# Thermit.net
KiCad netlist of a schematic drawn in Altium Designer
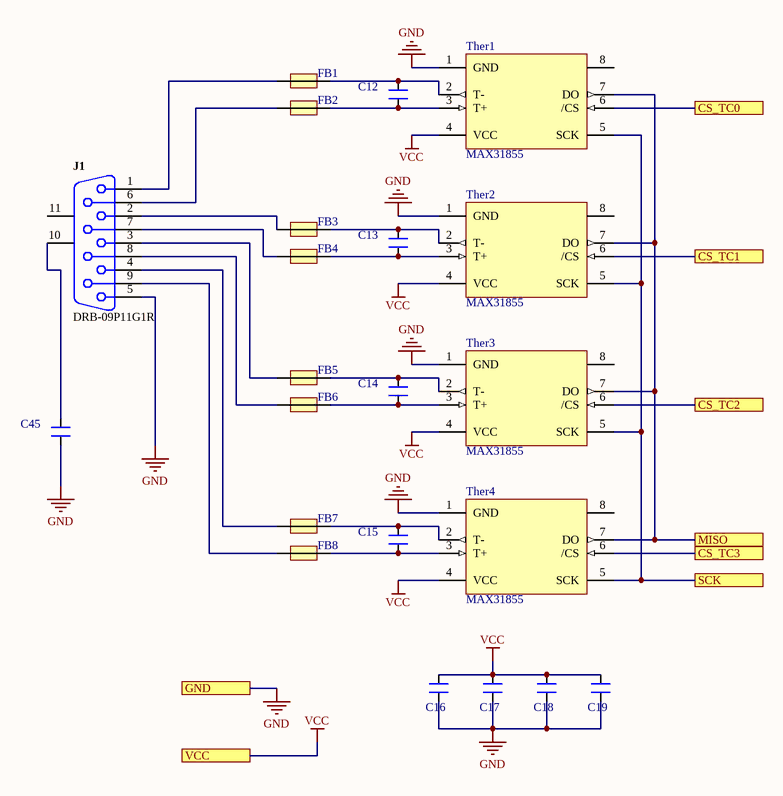
[diagram p0: Thermit.SchDoc]

(export (version "E")
  (design (tool "Eeschema 10.0.6"))
  (components
    (comp (ref "C12") (value "10nF") (footprint "CN-SMD-0603_big") (libsource (lib "nhan") (part "CN")))
    (comp (ref "C13") (value "10nF") (footprint "CN-SMD-0603_big") (libsource (lib "nhan") (part "CN")))
    (comp (ref "C14") (value "10nF") (footprint "CN-SMD-0603_big") (libsource (lib "nhan") (part "CN")))
    (comp (ref "C15") (value "10nF") (footprint "CN-SMD-0603_big") (libsource (lib "nhan") (part "CN")))
    (comp (ref "C16") (value "100nF") (footprint "CN-SMD-0603_big") (libsource (lib "nhan") (part "CN")))
    (comp (ref "C17") (value "100nF") (footprint "CN-SMD-0603_big") (libsource (lib "nhan") (part "CN")))
    (comp (ref "C18") (value "100nF") (footprint "CN-SMD-0603_big") (libsource (lib "nhan") (part "CN")))
    (comp (ref "C19") (value "100nF") (footprint "CN-SMD-0603_big") (libsource (lib "nhan") (part "CN")))
    (comp (ref "C45") (value "10nF") (footprint "CN-SMD-0603_big") (libsource (lib "nhan") (part "CN")))
    (comp (ref "FB1") (value "FB") (footprint "Capacitor_805") (libsource (lib "nhan") (part "FB")))
    (comp (ref "FB2") (value "FB") (footprint "Capacitor_805") (libsource (lib "nhan") (part "FB")))
    (comp (ref "FB3") (value "FB") (footprint "Capacitor_805") (libsource (lib "nhan") (part "FB")))
    (comp (ref "FB4") (value "FB") (footprint "Capacitor_805") (libsource (lib "nhan") (part "FB")))
    (comp (ref "FB5") (value "FB") (footprint "Capacitor_805") (libsource (lib "nhan") (part "FB")))
    (comp (ref "FB6") (value "FB") (footprint "Capacitor_805") (libsource (lib "nhan") (part "FB")))
    (comp (ref "FB7") (value "FB") (footprint "Capacitor_805") (libsource (lib "nhan") (part "FB")))
    (comp (ref "FB8") (value "FB") (footprint "Capacitor_805") (libsource (lib "nhan") (part "FB")))
    (comp (ref "J1")
      (value "DRB-09P11G1R")
      (footprint "DB9_MALE")
      (description "Connector, DB9 R/A Through-hole Male")
      (libsource (lib "LIBRARY") (part "CON 9 Male"))
    )
    (comp (ref "Ther1") (value "MAX31855") (footprint "SO8") (libsource (lib "nhan") (part "MAX31855")))
    (comp (ref "Ther2") (value "MAX31855") (footprint "SO8") (libsource (lib "nhan") (part "MAX31855")))
    (comp (ref "Ther3") (value "MAX31855") (footprint "SO8") (libsource (lib "nhan") (part "MAX31855")))
    (comp (ref "Ther4") (value "MAX31855") (footprint "SO8") (libsource (lib "nhan") (part "MAX31855")))
  )
  (nets
    (net (code "1") (name "/CS_TC0") (class "Default")
      (node (ref "Ther1") (pin "6") (pinfunction "/CS_6") (pintype "input"))
    )
    (net (code "2") (name "/CS_TC1") (class "Default")
      (node (ref "Ther2") (pin "6") (pinfunction "/CS_6") (pintype "input"))
    )
    (net (code "3") (name "/CS_TC2") (class "Default")
      (node (ref "Ther3") (pin "6") (pinfunction "/CS_6") (pintype "input"))
    )
    (net (code "4") (name "/CS_TC3") (class "Default")
      (node (ref "Ther4") (pin "6") (pinfunction "/CS_6") (pintype "input"))
    )
    (net (code "5") (name "/MISO") (class "Default")
      (node (ref "Ther1") (pin "7") (pinfunction "DO_7") (pintype "output"))
      (node (ref "Ther2") (pin "7") (pinfunction "DO_7") (pintype "output"))
      (node (ref "Ther3") (pin "7") (pinfunction "DO_7") (pintype "output"))
      (node (ref "Ther4") (pin "7") (pinfunction "DO_7") (pintype "output"))
    )
    (net (code "6") (name "/SCK") (class "Default")
      (node (ref "Ther1") (pin "5") (pinfunction "SCK_5") (pintype "passive"))
      (node (ref "Ther2") (pin "5") (pinfunction "SCK_5") (pintype "passive"))
      (node (ref "Ther3") (pin "5") (pinfunction "SCK_5") (pintype "passive"))
      (node (ref "Ther4") (pin "5") (pinfunction "SCK_5") (pintype "passive"))
    )
    (net (code "7") (name "GND") (class "Default")
      (node (ref "C16") (pin "1") (pinfunction "1_1") (pintype "passive"))
      (node (ref "C17") (pin "1") (pinfunction "1_1") (pintype "passive"))
      (node (ref "C18") (pin "1") (pinfunction "1_1") (pintype "passive"))
      (node (ref "C19") (pin "1") (pinfunction "1_1") (pintype "passive"))
      (node (ref "C45") (pin "1") (pinfunction "1_1") (pintype "passive"))
      (node (ref "J1") (pin "5") (pinfunction "5_5") (pintype "passive"))
      (node (ref "Ther1") (pin "1") (pinfunction "GND_1") (pintype "passive"))
      (node (ref "Ther2") (pin "1") (pinfunction "GND_1") (pintype "passive"))
      (node (ref "Ther3") (pin "1") (pinfunction "GND_1") (pintype "passive"))
      (node (ref "Ther4") (pin "1") (pinfunction "GND_1") (pintype "passive"))
    )
    (net (code "8") (name "Net-(FB1-Pad1)") (class "Default")
      (node (ref "FB1") (pin "1") (pinfunction "1_1") (pintype "passive"))
      (node (ref "J1") (pin "1") (pinfunction "1_1") (pintype "passive"))
    )
    (net (code "9") (name "Net-(FB2-Pad1)") (class "Default")
      (node (ref "FB2") (pin "1") (pinfunction "1_1") (pintype "passive"))
      (node (ref "J1") (pin "6") (pinfunction "6_6") (pintype "passive"))
    )
    (net (code "10") (name "Net-(FB3-Pad1)") (class "Default")
      (node (ref "FB3") (pin "1") (pinfunction "1_1") (pintype "passive"))
      (node (ref "J1") (pin "2") (pinfunction "2_2") (pintype "passive"))
    )
    (net (code "11") (name "Net-(FB4-Pad1)") (class "Default")
      (node (ref "FB4") (pin "1") (pinfunction "1_1") (pintype "passive"))
      (node (ref "J1") (pin "7") (pinfunction "7_7") (pintype "passive"))
    )
    (net (code "12") (name "Net-(FB5-Pad1)") (class "Default")
      (node (ref "FB5") (pin "1") (pinfunction "1_1") (pintype "passive"))
      (node (ref "J1") (pin "3") (pinfunction "3_3") (pintype "passive"))
    )
    (net (code "13") (name "Net-(FB6-Pad1)") (class "Default")
      (node (ref "FB6") (pin "1") (pinfunction "1_1") (pintype "passive"))
      (node (ref "J1") (pin "8") (pinfunction "8_8") (pintype "passive"))
    )
    (net (code "14") (name "Net-(FB7-Pad1)") (class "Default")
      (node (ref "FB7") (pin "1") (pinfunction "1_1") (pintype "passive"))
      (node (ref "J1") (pin "4") (pinfunction "4_4") (pintype "passive"))
    )
    (net (code "15") (name "Net-(FB8-Pad1)") (class "Default")
      (node (ref "FB8") (pin "1") (pinfunction "1_1") (pintype "passive"))
      (node (ref "J1") (pin "9") (pinfunction "9_9") (pintype "passive"))
    )
    (net (code "16") (name "Net-(J1-MH1)") (class "Default")
      (node (ref "C45") (pin "2") (pinfunction "2_2") (pintype "passive"))
      (node (ref "J1") (pin "10") (pinfunction "MH1_10") (pintype "passive"))
    )
    (net (code "17") (name "Net-(Ther1-T+)") (class "Default")
      (node (ref "C12") (pin "1") (pinfunction "1_1") (pintype "passive"))
      (node (ref "FB2") (pin "2") (pinfunction "2_2") (pintype "passive"))
      (node (ref "Ther1") (pin "3") (pinfunction "T+_3") (pintype "input"))
    )
    (net (code "18") (name "Net-(Ther1-T-)") (class "Default")
      (node (ref "C12") (pin "2") (pinfunction "2_2") (pintype "passive"))
      (node (ref "FB1") (pin "2") (pinfunction "2_2") (pintype "passive"))
      (node (ref "Ther1") (pin "2") (pinfunction "T-_2") (pintype "output"))
    )
    (net (code "19") (name "Net-(Ther2-T+)") (class "Default")
      (node (ref "C13") (pin "1") (pinfunction "1_1") (pintype "passive"))
      (node (ref "FB4") (pin "2") (pinfunction "2_2") (pintype "passive"))
      (node (ref "Ther2") (pin "3") (pinfunction "T+_3") (pintype "input"))
    )
    (net (code "20") (name "Net-(Ther2-T-)") (class "Default")
      (node (ref "C13") (pin "2") (pinfunction "2_2") (pintype "passive"))
      (node (ref "FB3") (pin "2") (pinfunction "2_2") (pintype "passive"))
      (node (ref "Ther2") (pin "2") (pinfunction "T-_2") (pintype "output"))
    )
    (net (code "21") (name "Net-(Ther3-T+)") (class "Default")
      (node (ref "C14") (pin "1") (pinfunction "1_1") (pintype "passive"))
      (node (ref "FB6") (pin "2") (pinfunction "2_2") (pintype "passive"))
      (node (ref "Ther3") (pin "3") (pinfunction "T+_3") (pintype "input"))
    )
    (net (code "22") (name "Net-(Ther3-T-)") (class "Default")
      (node (ref "C14") (pin "2") (pinfunction "2_2") (pintype "passive"))
      (node (ref "FB5") (pin "2") (pinfunction "2_2") (pintype "passive"))
      (node (ref "Ther3") (pin "2") (pinfunction "T-_2") (pintype "output"))
    )
    (net (code "23") (name "Net-(Ther4-T+)") (class "Default")
      (node (ref "C15") (pin "1") (pinfunction "1_1") (pintype "passive"))
      (node (ref "FB8") (pin "2") (pinfunction "2_2") (pintype "passive"))
      (node (ref "Ther4") (pin "3") (pinfunction "T+_3") (pintype "input"))
    )
    (net (code "24") (name "Net-(Ther4-T-)") (class "Default")
      (node (ref "C15") (pin "2") (pinfunction "2_2") (pintype "passive"))
      (node (ref "FB7") (pin "2") (pinfunction "2_2") (pintype "passive"))
      (node (ref "Ther4") (pin "2") (pinfunction "T-_2") (pintype "output"))
    )
    (net (code "25") (name "VCC") (class "Default")
      (node (ref "C16") (pin "2") (pinfunction "2_2") (pintype "passive"))
      (node (ref "C17") (pin "2") (pinfunction "2_2") (pintype "passive"))
      (node (ref "C18") (pin "2") (pinfunction "2_2") (pintype "passive"))
      (node (ref "C19") (pin "2") (pinfunction "2_2") (pintype "passive"))
      (node (ref "Ther1") (pin "4") (pinfunction "VCC_4") (pintype "passive"))
      (node (ref "Ther2") (pin "4") (pinfunction "VCC_4") (pintype "passive"))
      (node (ref "Ther3") (pin "4") (pinfunction "VCC_4") (pintype "passive"))
      (node (ref "Ther4") (pin "4") (pinfunction "VCC_4") (pintype "passive"))
    )
    (net (code "26") (name "unconnected-(J1-MH2-Pad11)") (class "Default")
      (node (ref "J1") (pin "11") (pinfunction "MH2_11") (pintype "passive"))
    )
    (net (code "27") (name "unconnected-(Ther1-Pad8)") (class "Default")
      (node (ref "Ther1") (pin "8") (pintype "passive"))
    )
    (net (code "28") (name "unconnected-(Ther2-Pad8)") (class "Default")
      (node (ref "Ther2") (pin "8") (pintype "passive"))
    )
    (net (code "29") (name "unconnected-(Ther3-Pad8)") (class "Default")
      (node (ref "Ther3") (pin "8") (pintype "passive"))
    )
    (net (code "30") (name "unconnected-(Ther4-Pad8)") (class "Default")
      (node (ref "Ther4") (pin "8") (pintype "passive"))
    )
  )
)
